# power_board2_v1_0.net
KiCad netlist of a schematic drawn in EAGLE
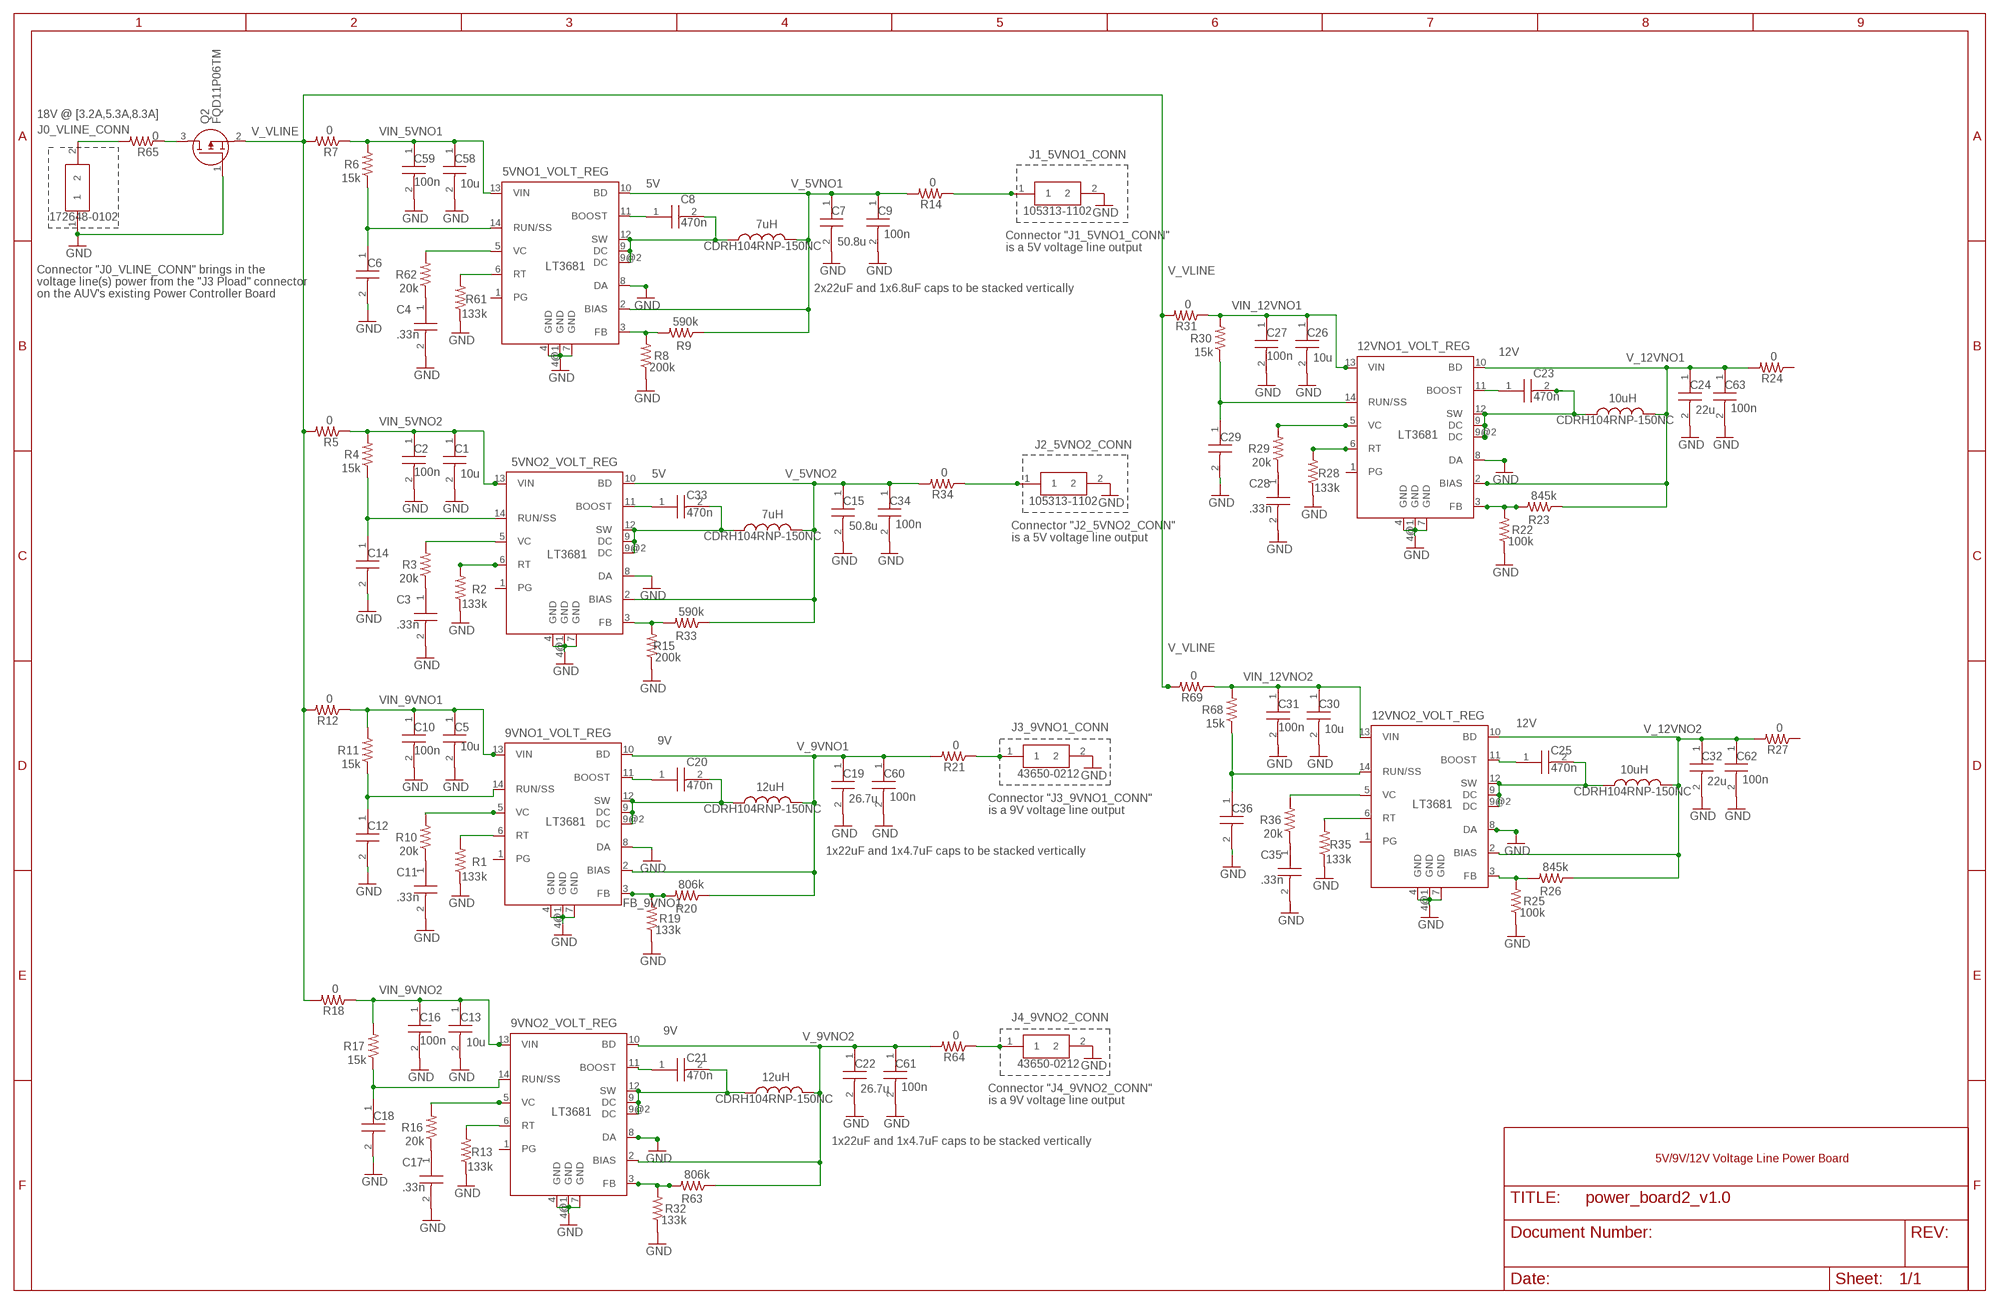
[diagram p0: schematic, sheet 1]

(export (version "E")
  (design (tool "Eeschema 10.0.6"))
  (components
    (comp (ref "5VNO1_VOLT_REG")
      (value "LT3681")
      (footprint "eagle-import:DFN14-4X3DE")
      (fields (field (name "MPN") "LT3681EDE#PBF"))
      (libsource (lib "eagle-import") (part "LT3681"))
    )
    (comp (ref "5VNO2_VOLT_REG")
      (value "LT3681")
      (footprint "eagle-import:DFN14-4X3DE")
      (fields (field (name "MPN") "LT3681EDE#PBF"))
      (libsource (lib "eagle-import") (part "LT3681"))
    )
    (comp (ref "9VNO1_VOLT_REG")
      (value "LT3681")
      (footprint "eagle-import:DFN14-4X3DE")
      (fields (field (name "MPN") "LT3681EDE#PBF"))
      (libsource (lib "eagle-import") (part "LT3681"))
    )
    (comp (ref "9VNO2_VOLT_REG")
      (value "LT3681")
      (footprint "eagle-import:DFN14-4X3DE")
      (fields (field (name "MPN") "LT3681EDE#PBF"))
      (libsource (lib "eagle-import") (part "LT3681"))
    )
    (comp (ref "12VNO1_VOLT_REG")
      (value "LT3681")
      (footprint "eagle-import:DFN14-4X3DE")
      (fields (field (name "MPN") "LT3681EDE#PBF"))
      (libsource (lib "eagle-import") (part "LT3681"))
    )
    (comp (ref "12VNO2_VOLT_REG")
      (value "LT3681")
      (footprint "eagle-import:DFN14-4X3DE")
      (fields (field (name "MPN") "LT3681EDE#PBF"))
      (libsource (lib "eagle-import") (part "LT3681"))
    )
    (comp (ref "C1")
      (value "10u")
      (footprint "eagle-import:CAPC5750X279N")
      (fields
        (field (name "MANUFACTURER_PART_NUMBER") "22201C106KAT2A")
        (field (name "MOUSER_PART_NUMBER") "581-22201C106KAT2A")
      )
      (libsource (lib "eagle-import") (part "22201C106KAT2A"))
    )
    (comp (ref "C2")
      (value "100n")
      (footprint "eagle-import:CAPC1608X90N")
      (fields
        (field (name "MANUFACTURER_PART_NUMBER") "06031C104KAT2A")
        (field (name "MOUSER_PART_NUMBER") "581-06031C104KAT2A")
      )
      (libsource (lib "eagle-import") (part "06031C104KAT2A"))
    )
    (comp (ref "C3")
      (value ".33n")
      (footprint "eagle-import:CAPC2012X140N")
      (fields
        (field (name "MANUFACTURER_PART_NUMBER") "08053C334KAT2A")
        (field (name "MOUSER_PART_NUMBER") "581-08053C334KAT2A")
        (field (name "RS_PART_NUMBER") "1747387")
      )
      (libsource (lib "eagle-import") (part "08053C334KAT2A"))
    )
    (comp (ref "C4")
      (value ".33n")
      (footprint "eagle-import:CAPC2012X140N")
      (fields
        (field (name "MANUFACTURER_PART_NUMBER") "08053C334KAT2A")
        (field (name "MOUSER_PART_NUMBER") "581-08053C334KAT2A")
        (field (name "RS_PART_NUMBER") "1747387")
      )
      (libsource (lib "eagle-import") (part "08053C334KAT2A"))
    )
    (comp (ref "C5")
      (value "10u")
      (footprint "eagle-import:CAPC5750X279N")
      (fields
        (field (name "MANUFACTURER_PART_NUMBER") "22201C106KAT2A")
        (field (name "MOUSER_PART_NUMBER") "581-22201C106KAT2A")
      )
      (libsource (lib "eagle-import") (part "22201C106KAT2A"))
    )
    (comp (ref "C6")
      (value "220n")
      (footprint "eagle-import:CAPC2012X140N")
      (fields
        (field (name "MANUFACTURER_PART_NUMBER") "08051C224KAT2A")
        (field (name "MOUSER_PART_NUMBER") "581-08051C224KAT2A")
      )
      (libsource (lib "eagle-import") (part "08051C224KAT2A"))
    )
    (comp (ref "C7")
      (value "50.8u")
      (footprint "eagle-import:CAPC3225X279N")
      (fields
        (field (name "MANUFACTURER_PART_NUMBER") "12103C226KAT2A")
        (field (name "MOUSER_PART_NUMBER") "581-12103C226KAT2A")
      )
      (libsource (lib "eagle-import") (part "12103C226KAT2A"))
    )
    (comp (ref "C8")
      (value "470n")
      (footprint "eagle-import:CAPC1608X90N")
      (fields
        (field (name "MANUFACTURER_PART_NUMBER") "06033C474JAT2A")
        (field (name "MOUSER_PART_NUMBER") "581-06033C474JAT2A")
      )
      (libsource (lib "eagle-import") (part "06033C474JAT2A"))
    )
    (comp (ref "C9")
      (value "100n")
      (footprint "eagle-import:CAPC1608X90N")
      (fields
        (field (name "MANUFACTURER_PART_NUMBER") "06033C104KAT4A")
        (field (name "MOUSER_PART_NUMBER") "581-06033C104KAT4A")
      )
      (libsource (lib "eagle-import") (part "06033C104KAT4A"))
    )
    (comp (ref "C10")
      (value "100n")
      (footprint "eagle-import:CAPC1608X90N")
      (fields
        (field (name "MANUFACTURER_PART_NUMBER") "06031C104KAT2A")
        (field (name "MOUSER_PART_NUMBER") "581-06031C104KAT2A")
      )
      (libsource (lib "eagle-import") (part "06031C104KAT2A"))
    )
    (comp (ref "C11")
      (value ".33n")
      (footprint "eagle-import:CAPC2012X140N")
      (fields
        (field (name "MANUFACTURER_PART_NUMBER") "08053C334KAT2A")
        (field (name "MOUSER_PART_NUMBER") "581-08053C334KAT2A")
        (field (name "RS_PART_NUMBER") "1747387")
      )
      (libsource (lib "eagle-import") (part "08053C334KAT2A"))
    )
    (comp (ref "C12")
      (value "220n")
      (footprint "eagle-import:CAPC2012X140N")
      (fields
        (field (name "MANUFACTURER_PART_NUMBER") "08051C224KAT2A")
        (field (name "MOUSER_PART_NUMBER") "581-08051C224KAT2A")
      )
      (libsource (lib "eagle-import") (part "08051C224KAT2A"))
    )
    (comp (ref "C13")
      (value "10u")
      (footprint "eagle-import:CAPC5750X279N")
      (fields
        (field (name "MANUFACTURER_PART_NUMBER") "22201C106KAT2A")
        (field (name "MOUSER_PART_NUMBER") "581-22201C106KAT2A")
      )
      (libsource (lib "eagle-import") (part "22201C106KAT2A"))
    )
    (comp (ref "C14")
      (value "220n")
      (footprint "eagle-import:CAPC2012X140N")
      (fields
        (field (name "MANUFACTURER_PART_NUMBER") "08051C224KAT2A")
        (field (name "MOUSER_PART_NUMBER") "581-08051C224KAT2A")
      )
      (libsource (lib "eagle-import") (part "08051C224KAT2A"))
    )
    (comp (ref "C15")
      (value "50.8u")
      (footprint "eagle-import:CAPC3225X279N")
      (fields
        (field (name "MANUFACTURER_PART_NUMBER") "12103C226KAT2A")
        (field (name "MOUSER_PART_NUMBER") "581-12103C226KAT2A")
      )
      (libsource (lib "eagle-import") (part "12103C226KAT2A"))
    )
    (comp (ref "C16")
      (value "100n")
      (footprint "eagle-import:CAPC1608X90N")
      (fields
        (field (name "MANUFACTURER_PART_NUMBER") "06031C104KAT2A")
        (field (name "MOUSER_PART_NUMBER") "581-06031C104KAT2A")
      )
      (libsource (lib "eagle-import") (part "06031C104KAT2A"))
    )
    (comp (ref "C17")
      (value ".33n")
      (footprint "eagle-import:CAPC2012X140N")
      (fields
        (field (name "MANUFACTURER_PART_NUMBER") "08053C334KAT2A")
        (field (name "MOUSER_PART_NUMBER") "581-08053C334KAT2A")
        (field (name "RS_PART_NUMBER") "1747387")
      )
      (libsource (lib "eagle-import") (part "08053C334KAT2A"))
    )
    (comp (ref "C18")
      (value "220n")
      (footprint "eagle-import:CAPC2012X140N")
      (fields
        (field (name "MANUFACTURER_PART_NUMBER") "08051C224KAT2A")
        (field (name "MOUSER_PART_NUMBER") "581-08051C224KAT2A")
      )
      (libsource (lib "eagle-import") (part "08051C224KAT2A"))
    )
    (comp (ref "C19")
      (value "26.7u")
      (footprint "eagle-import:CAPC3225X279N")
      (fields
        (field (name "MANUFACTURER_PART_NUMBER") "12103C226KAT2A")
        (field (name "MOUSER_PART_NUMBER") "581-12103C226KAT2A")
      )
      (libsource (lib "eagle-import") (part "12103C226KAT2A"))
    )
    (comp (ref "C20")
      (value "470n")
      (footprint "eagle-import:CAPC1608X90N")
      (fields
        (field (name "MANUFACTURER_PART_NUMBER") "06033C474JAT2A")
        (field (name "MOUSER_PART_NUMBER") "581-06033C474JAT2A")
      )
      (libsource (lib "eagle-import") (part "06033C474JAT2A"))
    )
    (comp (ref "C21")
      (value "470n")
      (footprint "eagle-import:CAPC1608X90N")
      (fields
        (field (name "MANUFACTURER_PART_NUMBER") "06033C474JAT2A")
        (field (name "MOUSER_PART_NUMBER") "581-06033C474JAT2A")
      )
      (libsource (lib "eagle-import") (part "06033C474JAT2A"))
    )
    (comp (ref "C22")
      (value "26.7u")
      (footprint "eagle-import:CAPC3225X279N")
      (fields
        (field (name "MANUFACTURER_PART_NUMBER") "12103C226KAT2A")
        (field (name "MOUSER_PART_NUMBER") "581-12103C226KAT2A")
      )
      (libsource (lib "eagle-import") (part "12103C226KAT2A"))
    )
    (comp (ref "C23")
      (value "470n")
      (footprint "eagle-import:CAPC1608X90N")
      (fields
        (field (name "MANUFACTURER_PART_NUMBER") "06033C474JAT2A")
        (field (name "MOUSER_PART_NUMBER") "581-06033C474JAT2A")
      )
      (libsource (lib "eagle-import") (part "06033C474JAT2A"))
    )
    (comp (ref "C24")
      (value "50.8u")
      (footprint "eagle-import:CAPC3225X279N")
      (fields
        (field (name "MANUFACTURER_PART_NUMBER") "12103C226KAT2A")
        (field (name "MOUSER_PART_NUMBER") "581-12103C226KAT2A")
      )
      (libsource (lib "eagle-import") (part "12103C226KAT2A"))
    )
    (comp (ref "C25")
      (value "470n")
      (footprint "eagle-import:CAPC1608X90N")
      (fields
        (field (name "MANUFACTURER_PART_NUMBER") "06033C474JAT2A")
        (field (name "MOUSER_PART_NUMBER") "581-06033C474JAT2A")
      )
      (libsource (lib "eagle-import") (part "06033C474JAT2A"))
    )
    (comp (ref "C26")
      (value "10u")
      (footprint "eagle-import:CAPC5750X279N")
      (fields
        (field (name "MANUFACTURER_PART_NUMBER") "22201C106KAT2A")
        (field (name "MOUSER_PART_NUMBER") "581-22201C106KAT2A")
      )
      (libsource (lib "eagle-import") (part "22201C106KAT2A"))
    )
    (comp (ref "C27")
      (value "100n")
      (footprint "eagle-import:CAPC1608X90N")
      (fields
        (field (name "MANUFACTURER_PART_NUMBER") "06031C104KAT2A")
        (field (name "MOUSER_PART_NUMBER") "581-06031C104KAT2A")
      )
      (libsource (lib "eagle-import") (part "06031C104KAT2A"))
    )
    (comp (ref "C28")
      (value ".33n")
      (footprint "eagle-import:CAPC2012X140N")
      (fields
        (field (name "MANUFACTURER_PART_NUMBER") "08053C334KAT2A")
        (field (name "MOUSER_PART_NUMBER") "581-08053C334KAT2A")
        (field (name "RS_PART_NUMBER") "1747387")
      )
      (libsource (lib "eagle-import") (part "08053C334KAT2A"))
    )
    (comp (ref "C29")
      (value "220n")
      (footprint "eagle-import:CAPC2012X140N")
      (fields
        (field (name "MANUFACTURER_PART_NUMBER") "08051C224KAT2A")
        (field (name "MOUSER_PART_NUMBER") "581-08051C224KAT2A")
      )
      (libsource (lib "eagle-import") (part "08051C224KAT2A"))
    )
    (comp (ref "C30")
      (value "10u")
      (footprint "eagle-import:CAPC5750X279N")
      (fields
        (field (name "MANUFACTURER_PART_NUMBER") "22201C106KAT2A")
        (field (name "MOUSER_PART_NUMBER") "581-22201C106KAT2A")
      )
      (libsource (lib "eagle-import") (part "22201C106KAT2A"))
    )
    (comp (ref "C31")
      (value "100n")
      (footprint "eagle-import:CAPC1608X90N")
      (fields
        (field (name "MANUFACTURER_PART_NUMBER") "06031C104KAT2A")
        (field (name "MOUSER_PART_NUMBER") "581-06031C104KAT2A")
      )
      (libsource (lib "eagle-import") (part "06031C104KAT2A"))
    )
    (comp (ref "C32")
      (value "50.8u")
      (footprint "eagle-import:CAPC3225X279N")
      (fields
        (field (name "MANUFACTURER_PART_NUMBER") "12103C226KAT2A")
        (field (name "MOUSER_PART_NUMBER") "581-12103C226KAT2A")
      )
      (libsource (lib "eagle-import") (part "12103C226KAT2A"))
    )
    (comp (ref "C33")
      (value "470n")
      (footprint "eagle-import:CAPC1608X90N")
      (fields
        (field (name "MANUFACTURER_PART_NUMBER") "06033C474JAT2A")
        (field (name "MOUSER_PART_NUMBER") "581-06033C474JAT2A")
      )
      (libsource (lib "eagle-import") (part "06033C474JAT2A"))
    )
    (comp (ref "C34")
      (value "100n")
      (footprint "eagle-import:CAPC1608X90N")
      (fields
        (field (name "MANUFACTURER_PART_NUMBER") "06033C104KAT4A")
        (field (name "MOUSER_PART_NUMBER") "581-06033C104KAT4A")
      )
      (libsource (lib "eagle-import") (part "06033C104KAT4A"))
    )
    (comp (ref "C35")
      (value ".33n")
      (footprint "eagle-import:CAPC2012X140N")
      (fields
        (field (name "MANUFACTURER_PART_NUMBER") "08053C334KAT2A")
        (field (name "MOUSER_PART_NUMBER") "581-08053C334KAT2A")
        (field (name "RS_PART_NUMBER") "1747387")
      )
      (libsource (lib "eagle-import") (part "08053C334KAT2A"))
    )
    (comp (ref "C36")
      (value "220n")
      (footprint "eagle-import:CAPC2012X140N")
      (fields
        (field (name "MANUFACTURER_PART_NUMBER") "08051C224KAT2A")
        (field (name "MOUSER_PART_NUMBER") "581-08051C224KAT2A")
      )
      (libsource (lib "eagle-import") (part "08051C224KAT2A"))
    )
    (comp (ref "C58")
      (value "10u")
      (footprint "eagle-import:CAPC5750X279N")
      (fields
        (field (name "MANUFACTURER_PART_NUMBER") "22201C106KAT2A")
        (field (name "MOUSER_PART_NUMBER") "581-22201C106KAT2A")
      )
      (libsource (lib "eagle-import") (part "22201C106KAT2A"))
    )
    (comp (ref "C59")
      (value "100n")
      (footprint "eagle-import:CAPC1608X90N")
      (fields
        (field (name "MANUFACTURER_PART_NUMBER") "06031C104KAT2A")
        (field (name "MOUSER_PART_NUMBER") "581-06031C104KAT2A")
      )
      (libsource (lib "eagle-import") (part "06031C104KAT2A"))
    )
    (comp (ref "C60")
      (value "100n")
      (footprint "eagle-import:CAPC1608X90N")
      (fields
        (field (name "MANUFACTURER_PART_NUMBER") "06033C104KAT4A")
        (field (name "MOUSER_PART_NUMBER") "581-06033C104KAT4A")
      )
      (libsource (lib "eagle-import") (part "06033C104KAT4A"))
    )
    (comp (ref "C61")
      (value "100n")
      (footprint "eagle-import:CAPC1608X90N")
      (fields
        (field (name "MANUFACTURER_PART_NUMBER") "06033C104KAT4A")
        (field (name "MOUSER_PART_NUMBER") "581-06033C104KAT4A")
      )
      (libsource (lib "eagle-import") (part "06033C104KAT4A"))
    )
    (comp (ref "C62")
      (value "100n")
      (footprint "eagle-import:CAPC1608X90N")
      (fields
        (field (name "MANUFACTURER_PART_NUMBER") "06033C104KAT4A")
        (field (name "MOUSER_PART_NUMBER") "581-06033C104KAT4A")
      )
      (libsource (lib "eagle-import") (part "06033C104KAT4A"))
    )
    (comp (ref "C63")
      (value "100n")
      (footprint "eagle-import:CAPC1608X90N")
      (fields
        (field (name "MANUFACTURER_PART_NUMBER") "06033C104KAT4A")
        (field (name "MOUSER_PART_NUMBER") "581-06033C104KAT4A")
      )
      (libsource (lib "eagle-import") (part "06033C104KAT4A"))
    )
    (comp (ref "INDUCTOR_2")
      (value "CDRH104RNP-150NC")
      (footprint "eagle-import:INDPM102100X400N")
      (fields (field (name "MOUSER_PART_NUMBER") "851-CDRH104RNP-150NC"))
      (libsource (lib "eagle-import") (part "CDRH104RNP-150NC"))
    )
    (comp (ref "INDUCTOR_4")
      (value "CDRH104RNP-150NC")
      (footprint "eagle-import:INDPM102100X400N")
      (fields (field (name "MOUSER_PART_NUMBER") "851-CDRH104RNP-150NC"))
      (libsource (lib "eagle-import") (part "CDRH104RNP-150NC"))
    )
    (comp (ref "INDUCTOR_5")
      (value "CDRH104RNP-150NC")
      (footprint "eagle-import:INDPM102100X400N")
      (fields (field (name "MOUSER_PART_NUMBER") "851-CDRH104RNP-150NC"))
      (libsource (lib "eagle-import") (part "CDRH104RNP-150NC"))
    )
    (comp (ref "INDUCTOR_6")
      (value "CDRH104RNP-150NC")
      (footprint "eagle-import:INDPM102100X400N")
      (fields (field (name "MOUSER_PART_NUMBER") "851-CDRH104RNP-150NC"))
      (libsource (lib "eagle-import") (part "CDRH104RNP-150NC"))
    )
    (comp (ref "INDUCTOR_7")
      (value "CDRH104RNP-150NC")
      (footprint "eagle-import:INDPM102100X400N")
      (fields (field (name "MOUSER_PART_NUMBER") "851-CDRH104RNP-150NC"))
      (libsource (lib "eagle-import") (part "CDRH104RNP-150NC"))
    )
    (comp (ref "INDUCTOR_8")
      (value "CDRH104RNP-150NC")
      (footprint "eagle-import:INDPM102100X400N")
      (fields (field (name "MOUSER_PART_NUMBER") "851-CDRH104RNP-150NC"))
      (libsource (lib "eagle-import") (part "CDRH104RNP-150NC"))
    )
    (comp (ref "J0_VLINE_CONN")
      (value "172648-0102")
      (footprint "eagle-import:1726480102")
      (fields (field (name "MOUSER_PART_NUMBER") "538-172648-0102"))
      (libsource (lib "eagle-import") (part "172648-0102"))
    )
    (comp (ref "J1_B3_CONN1")
      (value "105313-1102")
      (footprint "eagle-import:1053131102")
      (fields (field (name "MOUSER_PART_NUMBER") "538-105313-1102") (field (name "RS_PART_NUMBER") "1623686"))
      (libsource (lib "eagle-import") (part "105313-1102"))
    )
    (comp (ref "J1_B3_CONN2")
      (value "105313-1102")
      (footprint "eagle-import:1053131102")
      (fields (field (name "MOUSER_PART_NUMBER") "538-105313-1102") (field (name "RS_PART_NUMBER") "1623686"))
      (libsource (lib "eagle-import") (part "105313-1102"))
    )
    (comp (ref "J3_9VNO1_CONN")
      (value "43650-0212")
      (footprint "eagle-import:43650-0214")
      (fields (field (name "MOUSER_PART_NUMBER") "538-43650-0212") (field (name "RS_PART_NUMBER") "4476811P"))
      (libsource (lib "eagle-import") (part "43650-0212"))
    )
    (comp (ref "J4_9VNO2_CONN")
      (value "43650-0212")
      (footprint "eagle-import:43650-0214")
      (fields (field (name "MOUSER_PART_NUMBER") "538-43650-0212") (field (name "RS_PART_NUMBER") "4476811P"))
      (libsource (lib "eagle-import") (part "43650-0212"))
    )
    (comp (ref "Q2")
      (value "FQD11P06TM")
      (footprint "eagle-import:DPAK3-CASE-369AS")
      (fields (field (name "MOUSER_PART_NUMBER") "512-FQD11P06TM") (field (name "RS_PART_NUMBER") "6710949P"))
      (libsource (lib "eagle-import") (part "FQD11P06TM"))
    )
    (comp (ref "R1")
      (value "133k")
      (footprint "eagle-import:R0603")
      (libsource (lib "eagle-import") (part "R-US_R0603"))
    )
    (comp (ref "R2")
      (value "133k")
      (footprint "eagle-import:R0603")
      (libsource (lib "eagle-import") (part "R-US_R0603"))
    )
    (comp (ref "R3")
      (value "20k")
      (footprint "eagle-import:R0603")
      (libsource (lib "eagle-import") (part "R-US_R0603"))
    )
    (comp (ref "R4")
      (value "15k")
      (footprint "eagle-import:R0603")
      (libsource (lib "eagle-import") (part "R-US_R0603"))
    )
    (comp (ref "R5")
      (value "0")
      (footprint "eagle-import:0207_2V")
      (fields (field (name "MFR") "Yageo") (field (name "MPN") "RC0805FR-0710KL"))
      (libsource (lib "eagle-import") (part "R-US_0207/2V"))
    )
    (comp (ref "R6")
      (value "15k")
      (footprint "eagle-import:R0603")
      (libsource (lib "eagle-import") (part "R-US_R0603"))
    )
    (comp (ref "R7")
      (value "0")
      (footprint "eagle-import:0207_2V")
      (fields (field (name "MFR") "Yageo") (field (name "MPN") "RC0805FR-0710KL"))
      (libsource (lib "eagle-import") (part "R-US_0207/2V"))
    )
    (comp (ref "R8")
      (value "200k")
      (footprint "eagle-import:R0603")
      (libsource (lib "eagle-import") (part "R-US_R0603"))
    )
    (comp (ref "R9")
      (value "590k")
      (footprint "eagle-import:R0603")
      (libsource (lib "eagle-import") (part "R-US_R0603"))
    )
    (comp (ref "R10")
      (value "20k")
      (footprint "eagle-import:R0603")
      (libsource (lib "eagle-import") (part "R-US_R0603"))
    )
    (comp (ref "R11")
      (value "15k")
      (footprint "eagle-import:R0603")
      (libsource (lib "eagle-import") (part "R-US_R0603"))
    )
    (comp (ref "R12")
      (value "0")
      (footprint "eagle-import:0207_2V")
      (fields (field (name "MFR") "Yageo") (field (name "MPN") "RC0805FR-0710KL"))
      (libsource (lib "eagle-import") (part "R-US_0207/2V"))
    )
    (comp (ref "R13")
      (value "133k")
      (footprint "eagle-import:R0603")
      (libsource (lib "eagle-import") (part "R-US_R0603"))
    )
    (comp (ref "R14")
      (value "0")
      (footprint "eagle-import:0207_2V")
      (fields (field (name "MFR") "Yageo") (field (name "MPN") "RC0805FR-0710KL"))
      (libsource (lib "eagle-import") (part "R-US_0207/2V"))
    )
    (comp (ref "R15")
      (value "200k")
      (footprint "eagle-import:R0603")
      (libsource (lib "eagle-import") (part "R-US_R0603"))
    )
    (comp (ref "R16")
      (value "20k")
      (footprint "eagle-import:R0603")
      (libsource (lib "eagle-import") (part "R-US_R0603"))
    )
    (comp (ref "R17")
      (value "15k")
      (footprint "eagle-import:R0603")
      (libsource (lib "eagle-import") (part "R-US_R0603"))
    )
    (comp (ref "R18")
      (value "0")
      (footprint "eagle-import:0207_2V")
      (fields (field (name "MFR") "Yageo") (field (name "MPN") "RC0805FR-0710KL"))
      (libsource (lib "eagle-import") (part "R-US_0207/2V"))
    )
    (comp (ref "R19")
      (value "133k")
      (footprint "eagle-import:R0603")
      (libsource (lib "eagle-import") (part "R-US_R0603"))
    )
    (comp (ref "R20")
      (value "806k")
      (footprint "eagle-import:R0603")
      (libsource (lib "eagle-import") (part "R-US_R0603"))
    )
    (comp (ref "R21")
      (value "0")
      (footprint "eagle-import:0207_2V")
      (fields (field (name "MFR") "Yageo") (field (name "MPN") "RC0805FR-0710KL"))
      (libsource (lib "eagle-import") (part "R-US_0207/2V"))
    )
    (comp (ref "R22")
      (value "100k")
      (footprint "eagle-import:R0603")
      (libsource (lib "eagle-import") (part "R-US_R0603"))
    )
    (comp (ref "R23")
      (value "845k")
      (footprint "eagle-import:R0603")
      (libsource (lib "eagle-import") (part "R-US_R0603"))
    )
    (comp (ref "R24")
      (value "0")
      (footprint "eagle-import:0207_2V")
      (fields (field (name "MFR") "Yageo") (field (name "MPN") "RC0805FR-0710KL"))
      (libsource (lib "eagle-import") (part "R-US_0207/2V"))
    )
    (comp (ref "R25")
      (value "100k")
      (footprint "eagle-import:R0603")
      (libsource (lib "eagle-import") (part "R-US_R0603"))
    )
    (comp (ref "R26")
      (value "845k")
      (footprint "eagle-import:R0603")
      (libsource (lib "eagle-import") (part "R-US_R0603"))
    )
    (comp (ref "R27")
      (value "0")
      (footprint "eagle-import:0207_2V")
      (fields (field (name "MFR") "Yageo") (field (name "MPN") "RC0805FR-0710KL"))
      (libsource (lib "eagle-import") (part "R-US_0207/2V"))
    )
    (comp (ref "R28")
      (value "133k")
      (footprint "eagle-import:R0603")
      (libsource (lib "eagle-import") (part "R-US_R0603"))
    )
    (comp (ref "R29")
      (value "20k")
      (footprint "eagle-import:R0603")
      (libsource (lib "eagle-import") (part "R-US_R0603"))
    )
    (comp (ref "R30")
      (value "15k")
      (footprint "eagle-import:R0603")
      (libsource (lib "eagle-import") (part "R-US_R0603"))
    )
    (comp (ref "R31")
      (value "0")
      (footprint "eagle-import:0207_2V")
      (fields (field (name "MFR") "Yageo") (field (name "MPN") "RC0805FR-0710KL"))
      (libsource (lib "eagle-import") (part "R-US_0207/2V"))
    )
    (comp (ref "R32")
      (value "133k")
      (footprint "eagle-import:R0603")
      (libsource (lib "eagle-import") (part "R-US_R0603"))
    )
    (comp (ref "R33")
      (value "590k")
      (footprint "eagle-import:R0603")
      (libsource (lib "eagle-import") (part "R-US_R0603"))
    )
    (comp (ref "R34")
      (value "0")
      (footprint "eagle-import:0207_2V")
      (fields (field (name "MFR") "Yageo") (field (name "MPN") "RC0805FR-0710KL"))
      (libsource (lib "eagle-import") (part "R-US_0207/2V"))
    )
    (comp (ref "R35")
      (value "133k")
      (footprint "eagle-import:R0603")
      (libsource (lib "eagle-import") (part "R-US_R0603"))
    )
    (comp (ref "R36")
      (value "20k")
      (footprint "eagle-import:R0603")
      (libsource (lib "eagle-import") (part "R-US_R0603"))
    )
    (comp (ref "R61")
      (value "133k")
      (footprint "eagle-import:R0603")
      (libsource (lib "eagle-import") (part "R-US_R0603"))
    )
    (comp (ref "R62")
      (value "20k")
      (footprint "eagle-import:R0603")
      (libsource (lib "eagle-import") (part "R-US_R0603"))
    )
    (comp (ref "R63")
      (value "806k")
      (footprint "eagle-import:R0603")
      (libsource (lib "eagle-import") (part "R-US_R0603"))
    )
    (comp (ref "R64")
      (value "0")
      (footprint "eagle-import:0207_2V")
      (fields (field (name "MFR") "Yageo") (field (name "MPN") "RC0805FR-0710KL"))
      (libsource (lib "eagle-import") (part "R-US_0207/2V"))
    )
    (comp (ref "R65")
      (value "0")
      (footprint "eagle-import:0207_2V")
      (fields (field (name "MFR") "Yageo") (field (name "MPN") "RC0805FR-0710KL"))
      (libsource (lib "eagle-import") (part "R-US_0207/2V"))
    )
    (comp (ref "R68")
      (value "15k")
      (footprint "eagle-import:R0603")
      (libsource (lib "eagle-import") (part "R-US_R0603"))
    )
    (comp (ref "R69")
      (value "0")
      (footprint "eagle-import:0207_2V")
      (fields (field (name "MFR") "Yageo") (field (name "MPN") "RC0805FR-0710KL"))
      (libsource (lib "eagle-import") (part "R-US_0207/2V"))
    )
  )
  (nets
    (net (code "1") (name "/FB_9VNO1") (class "Default")
      (node (ref "9VNO1_VOLT_REG") (pin "3") (pinfunction "FB_3") (pintype "input"))
      (node (ref "R19") (pin "2") (pinfunction "2_2") (pintype "passive"))
      (node (ref "R20") (pin "2") (pinfunction "2_2") (pintype "passive"))
    )
    (net (code "2") (name "/VIN_5VNO1") (class "Default")
      (node (ref "5VNO1_VOLT_REG") (pin "13") (pinfunction "VIN_13") (pintype "input"))
      (node (ref "C58") (pin "1") (pinfunction "1_1") (pintype "bidirectional"))
      (node (ref "C59") (pin "1") (pinfunction "1_1") (pintype "bidirectional"))
      (node (ref "R6") (pin "2") (pinfunction "2_2") (pintype "passive"))
      (node (ref "R7") (pin "1") (pinfunction "1_1") (pintype "passive"))
    )
    (net (code "3") (name "/VIN_5VNO2") (class "Default")
      (node (ref "5VNO2_VOLT_REG") (pin "13") (pinfunction "VIN_13") (pintype "input"))
      (node (ref "C1") (pin "1") (pinfunction "1_1") (pintype "bidirectional"))
      (node (ref "C2") (pin "1") (pinfunction "1_1") (pintype "bidirectional"))
      (node (ref "R4") (pin "2") (pinfunction "2_2") (pintype "passive"))
      (node (ref "R5") (pin "1") (pinfunction "1_1") (pintype "passive"))
    )
    (net (code "4") (name "/VIN_9VNO1") (class "Default")
      (node (ref "9VNO1_VOLT_REG") (pin "13") (pinfunction "VIN_13") (pintype "input"))
      (node (ref "C10") (pin "1") (pinfunction "1_1") (pintype "bidirectional"))
      (node (ref "C5") (pin "1") (pinfunction "1_1") (pintype "bidirectional"))
      (node (ref "R11") (pin "2") (pinfunction "2_2") (pintype "passive"))
      (node (ref "R12") (pin "1") (pinfunction "1_1") (pintype "passive"))
    )
    (net (code "5") (name "/VIN_9VNO2") (class "Default")
      (node (ref "9VNO2_VOLT_REG") (pin "13") (pinfunction "VIN_13") (pintype "input"))
      (node (ref "C13") (pin "1") (pinfunction "1_1") (pintype "bidirectional"))
      (node (ref "C16") (pin "1") (pinfunction "1_1") (pintype "bidirectional"))
      (node (ref "R17") (pin "2") (pinfunction "2_2") (pintype "passive"))
      (node (ref "R18") (pin "1") (pinfunction "1_1") (pintype "passive"))
    )
    (net (code "6") (name "/VIN_12VNO1") (class "Default")
      (node (ref "12VNO1_VOLT_REG") (pin "13") (pinfunction "VIN_13") (pintype "input"))
      (node (ref "C26") (pin "1") (pinfunction "1_1") (pintype "bidirectional"))
      (node (ref "C27") (pin "1") (pinfunction "1_1") (pintype "bidirectional"))
      (node (ref "R30") (pin "2") (pinfunction "2_2") (pintype "passive"))
      (node (ref "R31") (pin "1") (pinfunction "1_1") (pintype "passive"))
    )
    (net (code "7") (name "/VIN_12VNO2") (class "Default")
      (node (ref "12VNO2_VOLT_REG") (pin "13") (pinfunction "VIN_13") (pintype "input"))
      (node (ref "C30") (pin "1") (pinfunction "1_1") (pintype "bidirectional"))
      (node (ref "C31") (pin "1") (pinfunction "1_1") (pintype "bidirectional"))
      (node (ref "R68") (pin "2") (pinfunction "2_2") (pintype "passive"))
      (node (ref "R69") (pin "1") (pinfunction "1_1") (pintype "passive"))
    )
    (net (code "8") (name "/V_5VNO1") (class "Default")
      (node (ref "5VNO1_VOLT_REG") (pin "10") (pinfunction "BD_10") (pintype "input"))
      (node (ref "5VNO1_VOLT_REG") (pin "2") (pinfunction "BIAS_2") (pintype "input"))
      (node (ref "C7") (pin "1") (pinfunction "1_1") (pintype "bidirectional"))
      (node (ref "C9") (pin "1") (pinfunction "1_1") (pintype "bidirectional"))
      (node (ref "INDUCTOR_2") (pin "2") (pinfunction "2_2") (pintype "passive"))
      (node (ref "R14") (pin "2") (pinfunction "2_2") (pintype "passive"))
      (node (ref "R9") (pin "1") (pinfunction "1_1") (pintype "passive"))
    )
    (net (code "9") (name "/V_5VNO2") (class "Default")
      (node (ref "5VNO2_VOLT_REG") (pin "10") (pinfunction "BD_10") (pintype "input"))
      (node (ref "5VNO2_VOLT_REG") (pin "2") (pinfunction "BIAS_2") (pintype "input"))
      (node (ref "C15") (pin "1") (pinfunction "1_1") (pintype "bidirectional"))
      (node (ref "C34") (pin "1") (pinfunction "1_1") (pintype "bidirectional"))
      (node (ref "INDUCTOR_4") (pin "2") (pinfunction "2_2") (pintype "passive"))
      (node (ref "R33") (pin "1") (pinfunction "1_1") (pintype "passive"))
      (node (ref "R34") (pin "2") (pinfunction "2_2") (pintype "passive"))
    )
    (net (code "10") (name "/V_9VNO1") (class "Default")
      (node (ref "9VNO1_VOLT_REG") (pin "10") (pinfunction "BD_10") (pintype "input"))
      (node (ref "9VNO1_VOLT_REG") (pin "2") (pinfunction "BIAS_2") (pintype "input"))
      (node (ref "C19") (pin "1") (pinfunction "1_1") (pintype "bidirectional"))
      (node (ref "C60") (pin "1") (pinfunction "1_1") (pintype "bidirectional"))
      (node (ref "INDUCTOR_5") (pin "2") (pinfunction "2_2") (pintype "passive"))
      (node (ref "R20") (pin "1") (pinfunction "1_1") (pintype "passive"))
      (node (ref "R21") (pin "2") (pinfunction "2_2") (pintype "passive"))
    )
    (net (code "11") (name "/V_9VNO2") (class "Default")
      (node (ref "9VNO2_VOLT_REG") (pin "10") (pinfunction "BD_10") (pintype "input"))
      (node (ref "9VNO2_VOLT_REG") (pin "2") (pinfunction "BIAS_2") (pintype "input"))
      (node (ref "C22") (pin "1") (pinfunction "1_1") (pintype "bidirectional"))
      (node (ref "C61") (pin "1") (pinfunction "1_1") (pintype "bidirectional"))
      (node (ref "INDUCTOR_6") (pin "2") (pinfunction "2_2") (pintype "passive"))
      (node (ref "R63") (pin "1") (pinfunction "1_1") (pintype "passive"))
      (node (ref "R64") (pin "2") (pinfunction "2_2") (pintype "passive"))
    )
    (net (code "12") (name "/V_12VNO1") (class "Default")
      (node (ref "12VNO1_VOLT_REG") (pin "10") (pinfunction "BD_10") (pintype "input"))
      (node (ref "12VNO1_VOLT_REG") (pin "2") (pinfunction "BIAS_2") (pintype "input"))
      (node (ref "C24") (pin "1") (pinfunction "1_1") (pintype "bidirectional"))
      (node (ref "C63") (pin "1") (pinfunction "1_1") (pintype "bidirectional"))
      (node (ref "INDUCTOR_7") (pin "2") (pinfunction "2_2") (pintype "passive"))
      (node (ref "R23") (pin "1") (pinfunction "1_1") (pintype "passive"))
      (node (ref "R24") (pin "2") (pinfunction "2_2") (pintype "passive"))
    )
    (net (code "13") (name "/V_12VNO2") (class "Default")
      (node (ref "12VNO2_VOLT_REG") (pin "10") (pinfunction "BD_10") (pintype "input"))
      (node (ref "12VNO2_VOLT_REG") (pin "2") (pinfunction "BIAS_2") (pintype "input"))
      (node (ref "C32") (pin "1") (pinfunction "1_1") (pintype "bidirectional"))
      (node (ref "C62") (pin "1") (pinfunction "1_1") (pintype "bidirectional"))
      (node (ref "INDUCTOR_8") (pin "2") (pinfunction "2_2") (pintype "passive"))
      (node (ref "R26") (pin "1") (pinfunction "1_1") (pintype "passive"))
      (node (ref "R27") (pin "2") (pinfunction "2_2") (pintype "passive"))
    )
    (net (code "14") (name "/V_VLINE") (class "Default")
      (node (ref "Q2") (pin "2") (pinfunction "S_2") (pintype "bidirectional"))
      (node (ref "R12") (pin "2") (pinfunction "2_2") (pintype "passive"))
      (node (ref "R18") (pin "2") (pinfunction "2_2") (pintype "passive"))
      (node (ref "R31") (pin "2") (pinfunction "2_2") (pintype "passive"))
      (node (ref "R5") (pin "2") (pinfunction "2_2") (pintype "passive"))
      (node (ref "R69") (pin "2") (pinfunction "2_2") (pintype "passive"))
      (node (ref "R7") (pin "2") (pinfunction "2_2") (pintype "passive"))
    )
    (net (code "15") (name "GND") (class "Default")
      (node (ref "12VNO1_VOLT_REG") (pin "4") (pinfunction "GND_4") (pintype "input"))
      (node (ref "12VNO1_VOLT_REG") (pin "4@1") (pinfunction "GND_4@1") (pintype "input"))
      (node (ref "12VNO1_VOLT_REG") (pin "7") (pinfunction "GND_7") (pintype "input"))
      (node (ref "12VNO1_VOLT_REG") (pin "8") (pinfunction "DA_8") (pintype "passive"))
      (node (ref "12VNO2_VOLT_REG") (pin "4") (pinfunction "GND_4") (pintype "input"))
      (node (ref "12VNO2_VOLT_REG") (pin "4@1") (pinfunction "GND_4@1") (pintype "input"))
      (node (ref "12VNO2_VOLT_REG") (pin "7") (pinfunction "GND_7") (pintype "input"))
      (node (ref "5VNO1_VOLT_REG") (pin "4") (pinfunction "GND_4") (pintype "input"))
      (node (ref "5VNO1_VOLT_REG") (pin "4@1") (pinfunction "GND_4@1") (pintype "input"))
      (node (ref "5VNO1_VOLT_REG") (pin "7") (pinfunction "GND_7") (pintype "input"))
      (node (ref "5VNO1_VOLT_REG") (pin "8") (pinfunction "DA_8") (pintype "passive"))
      (node (ref "5VNO2_VOLT_REG") (pin "4") (pinfunction "GND_4") (pintype "input"))
      (node (ref "5VNO2_VOLT_REG") (pin "4@1") (pinfunction "GND_4@1") (pintype "input"))
      (node (ref "5VNO2_VOLT_REG") (pin "7") (pinfunction "GND_7") (pintype "input"))
      (node (ref "5VNO2_VOLT_REG") (pin "8") (pinfunction "DA_8") (pintype "passive"))
      (node (ref "9VNO1_VOLT_REG") (pin "4") (pinfunction "GND_4") (pintype "input"))
      (node (ref "9VNO1_VOLT_REG") (pin "4@1") (pinfunction "GND_4@1") (pintype "input"))
      (node (ref "9VNO1_VOLT_REG") (pin "7") (pinfunction "GND_7") (pintype "input"))
      (node (ref "9VNO1_VOLT_REG") (pin "8") (pinfunction "DA_8") (pintype "passive"))
      (node (ref "9VNO2_VOLT_REG") (pin "4") (pinfunction "GND_4") (pintype "input"))
      (node (ref "9VNO2_VOLT_REG") (pin "4@1") (pinfunction "GND_4@1") (pintype "input"))
      (node (ref "9VNO2_VOLT_REG") (pin "7") (pinfunction "GND_7") (pintype "input"))
      (node (ref "9VNO2_VOLT_REG") (pin "8") (pinfunction "DA_8") (pintype "passive"))
      (node (ref "C1") (pin "2") (pinfunction "2_2") (pintype "bidirectional"))
      (node (ref "C10") (pin "2") (pinfunction "2_2") (pintype "bidirectional"))
      (node (ref "C11") (pin "2") (pinfunction "2_2") (pintype "bidirectional"))
      (node (ref "C12") (pin "2") (pinfunction "2_2") (pintype "bidirectional"))
      (node (ref "C13") (pin "2") (pinfunction "2_2") (pintype "bidirectional"))
      (node (ref "C14") (pin "2") (pinfunction "2_2") (pintype "bidirectional"))
      (node (ref "C15") (pin "2") (pinfunction "2_2") (pintype "bidirectional"))
      (node (ref "C16") (pin "2") (pinfunction "2_2") (pintype "bidirectional"))
      (node (ref "C17") (pin "2") (pinfunction "2_2") (pintype "bidirectional"))
      (node (ref "C18") (pin "2") (pinfunction "2_2") (pintype "bidirectional"))
      (node (ref "C19") (pin "2") (pinfunction "2_2") (pintype "bidirectional"))
      (node (ref "C2") (pin "2") (pinfunction "2_2") (pintype "bidirectional"))
      (node (ref "C22") (pin "2") (pinfunction "2_2") (pintype "bidirectional"))
      (node (ref "C24") (pin "2") (pinfunction "2_2") (pintype "bidirectional"))
      (node (ref "C26") (pin "2") (pinfunction "2_2") (pintype "bidirectional"))
      (node (ref "C27") (pin "2") (pinfunction "2_2") (pintype "bidirectional"))
      (node (ref "C28") (pin "2") (pinfunction "2_2") (pintype "bidirectional"))
      (node (ref "C29") (pin "2") (pinfunction "2_2") (pintype "bidirectional"))
      (node (ref "C3") (pin "2") (pinfunction "2_2") (pintype "bidirectional"))
      (node (ref "C30") (pin "2") (pinfunction "2_2") (pintype "bidirectional"))
      (node (ref "C31") (pin "2") (pinfunction "2_2") (pintype "bidirectional"))
      (node (ref "C32") (pin "2") (pinfunction "2_2") (pintype "bidirectional"))
      (node (ref "C34") (pin "2") (pinfunction "2_2") (pintype "bidirectional"))
      (node (ref "C35") (pin "2") (pinfunction "2_2") (pintype "bidirectional"))
      (node (ref "C36") (pin "2") (pinfunction "2_2") (pintype "bidirectional"))
      (node (ref "C4") (pin "2") (pinfunction "2_2") (pintype "bidirectional"))
      (node (ref "C5") (pin "2") (pinfunction "2_2") (pintype "bidirectional"))
      (node (ref "C58") (pin "2") (pinfunction "2_2") (pintype "bidirectional"))
      (node (ref "C59") (pin "2") (pinfunction "2_2") (pintype "bidirectional"))
      (node (ref "C6") (pin "2") (pinfunction "2_2") (pintype "bidirectional"))
      (node (ref "C60") (pin "2") (pinfunction "2_2") (pintype "bidirectional"))
      (node (ref "C61") (pin "2") (pinfunction "2_2") (pintype "bidirectional"))
      (node (ref "C62") (pin "2") (pinfunction "2_2") (pintype "bidirectional"))
      (node (ref "C63") (pin "2") (pinfunction "2_2") (pintype "bidirectional"))
      (node (ref "C7") (pin "2") (pinfunction "2_2") (pintype "bidirectional"))
      (node (ref "C9") (pin "2") (pinfunction "2_2") (pintype "bidirectional"))
      (node (ref "J0_VLINE_CONN") (pin "1") (pinfunction "1_1") (pintype "bidirectional"))
      (node (ref "J1_B3_CONN1") (pin "2") (pinfunction "2_2") (pintype "bidirectional"))
      (node (ref "J1_B3_CONN2") (pin "2") (pinfunction "2_2") (pintype "bidirectional"))
      (node (ref "J3_9VNO1_CONN") (pin "2") (pinfunction "2_2") (pintype "bidirectional"))
      (node (ref "J4_9VNO2_CONN") (pin "2") (pinfunction "2_2") (pintype "bidirectional"))
      (node (ref "Q2") (pin "1") (pinfunction "G_1") (pintype "bidirectional"))
      (node (ref "R1") (pin "1") (pinfunction "1_1") (pintype "passive"))
      (node (ref "R13") (pin "1") (pinfunction "1_1") (pintype "passive"))
      (node (ref "R15") (pin "1") (pinfunction "1_1") (pintype "passive"))
      (node (ref "R19") (pin "1") (pinfunction "1_1") (pintype "passive"))
      (node (ref "R2") (pin "1") (pinfunction "1_1") (pintype "passive"))
      (node (ref "R22") (pin "1") (pinfunction "1_1") (pintype "passive"))
      (node (ref "R25") (pin "1") (pinfunction "1_1") (pintype "passive"))
      (node (ref "R28") (pin "1") (pinfunction "1_1") (pintype "passive"))
      (node (ref "R32") (pin "1") (pinfunction "1_1") (pintype "passive"))
      (node (ref "R35") (pin "1") (pinfunction "1_1") (pintype "passive"))
      (node (ref "R61") (pin "1") (pinfunction "1_1") (pintype "passive"))
      (node (ref "R8") (pin "1") (pinfunction "1_1") (pintype "passive"))
    )
    (net (code "16") (name "Net-(5VNO1_VOLT_REG-BOOST)") (class "Default")
      (node (ref "5VNO1_VOLT_REG") (pin "11") (pinfunction "BOOST_11") (pintype "output"))
      (node (ref "C8") (pin "1") (pinfunction "1_1") (pintype "bidirectional"))
    )
    (net (code "17") (name "Net-(5VNO1_VOLT_REG-FB)") (class "Default")
      (node (ref "5VNO1_VOLT_REG") (pin "3") (pinfunction "FB_3") (pintype "input"))
      (node (ref "R8") (pin "2") (pinfunction "2_2") (pintype "passive"))
      (node (ref "R9") (pin "2") (pinfunction "2_2") (pintype "passive"))
    )
    (net (code "18") (name "Net-(5VNO1_VOLT_REG-RT)") (class "Default")
      (node (ref "5VNO1_VOLT_REG") (pin "6") (pinfunction "RT_6") (pintype "input"))
      (node (ref "R61") (pin "2") (pinfunction "2_2") (pintype "passive"))
    )
    (net (code "19") (name "Net-(5VNO1_VOLT_REG-RUN{slash}SS)") (class "Default")
      (node (ref "5VNO1_VOLT_REG") (pin "14") (pinfunction "RUN/SS_14") (pintype "input"))
      (node (ref "C6") (pin "1") (pinfunction "1_1") (pintype "bidirectional"))
      (node (ref "R6") (pin "1") (pinfunction "1_1") (pintype "passive"))
    )
    (net (code "20") (name "Net-(5VNO1_VOLT_REG-SW)") (class "Default")
      (node (ref "5VNO1_VOLT_REG") (pin "12") (pinfunction "SW_12") (pintype "output"))
      (node (ref "5VNO1_VOLT_REG") (pin "9") (pinfunction "DC_9") (pintype "passive"))
      (node (ref "5VNO1_VOLT_REG") (pin "9@2") (pinfunction "DC_9@2") (pintype "passive"))
      (node (ref "C8") (pin "2") (pinfunction "2_2") (pintype "bidirectional"))
      (node (ref "INDUCTOR_2") (pin "1") (pinfunction "1_1") (pintype "passive"))
    )
    (net (code "21") (name "Net-(5VNO1_VOLT_REG-VC)") (class "Default")
      (node (ref "5VNO1_VOLT_REG") (pin "5") (pinfunction "VC_5") (pintype "output"))
      (node (ref "R62") (pin "2") (pinfunction "2_2") (pintype "passive"))
    )
    (net (code "22") (name "Net-(5VNO2_VOLT_REG-BOOST)") (class "Default")
      (node (ref "5VNO2_VOLT_REG") (pin "11") (pinfunction "BOOST_11") (pintype "output"))
      (node (ref "C33") (pin "1") (pinfunction "1_1") (pintype "bidirectional"))
    )
    (net (code "23") (name "Net-(5VNO2_VOLT_REG-FB)") (class "Default")
      (node (ref "5VNO2_VOLT_REG") (pin "3") (pinfunction "FB_3") (pintype "input"))
      (node (ref "R15") (pin "2") (pinfunction "2_2") (pintype "passive"))
      (node (ref "R33") (pin "2") (pinfunction "2_2") (pintype "passive"))
    )
    (net (code "24") (name "Net-(5VNO2_VOLT_REG-RT)") (class "Default")
      (node (ref "5VNO2_VOLT_REG") (pin "6") (pinfunction "RT_6") (pintype "input"))
      (node (ref "R2") (pin "2") (pinfunction "2_2") (pintype "passive"))
    )
    (net (code "25") (name "Net-(5VNO2_VOLT_REG-RUN{slash}SS)") (class "Default")
      (node (ref "5VNO2_VOLT_REG") (pin "14") (pinfunction "RUN/SS_14") (pintype "input"))
      (node (ref "C14") (pin "1") (pinfunction "1_1") (pintype "bidirectional"))
      (node (ref "R4") (pin "1") (pinfunction "1_1") (pintype "passive"))
    )
    (net (code "26") (name "Net-(5VNO2_VOLT_REG-SW)") (class "Default")
      (node (ref "5VNO2_VOLT_REG") (pin "12") (pinfunction "SW_12") (pintype "output"))
      (node (ref "5VNO2_VOLT_REG") (pin "9") (pinfunction "DC_9") (pintype "passive"))
      (node (ref "5VNO2_VOLT_REG") (pin "9@2") (pinfunction "DC_9@2") (pintype "passive"))
      (node (ref "C33") (pin "2") (pinfunction "2_2") (pintype "bidirectional"))
      (node (ref "INDUCTOR_4") (pin "1") (pinfunction "1_1") (pintype "passive"))
    )
    (net (code "27") (name "Net-(5VNO2_VOLT_REG-VC)") (class "Default")
      (node (ref "5VNO2_VOLT_REG") (pin "5") (pinfunction "VC_5") (pintype "output"))
      (node (ref "R3") (pin "2") (pinfunction "2_2") (pintype "passive"))
    )
    (net (code "28") (name "Net-(9VNO1_VOLT_REG-BOOST)") (class "Default")
      (node (ref "9VNO1_VOLT_REG") (pin "11") (pinfunction "BOOST_11") (pintype "output"))
      (node (ref "C20") (pin "1") (pinfunction "1_1") (pintype "bidirectional"))
    )
    (net (code "29") (name "Net-(9VNO1_VOLT_REG-RT)") (class "Default")
      (node (ref "9VNO1_VOLT_REG") (pin "6") (pinfunction "RT_6") (pintype "input"))
      (node (ref "R1") (pin "2") (pinfunction "2_2") (pintype "passive"))
    )
    (net (code "30") (name "Net-(9VNO1_VOLT_REG-RUN{slash}SS)") (class "Default")
      (node (ref "9VNO1_VOLT_REG") (pin "14") (pinfunction "RUN/SS_14") (pintype "input"))
      (node (ref "C12") (pin "1") (pinfunction "1_1") (pintype "bidirectional"))
      (node (ref "R11") (pin "1") (pinfunction "1_1") (pintype "passive"))
    )
    (net (code "31") (name "Net-(9VNO1_VOLT_REG-SW)") (class "Default")
      (node (ref "9VNO1_VOLT_REG") (pin "12") (pinfunction "SW_12") (pintype "output"))
      (node (ref "9VNO1_VOLT_REG") (pin "9") (pinfunction "DC_9") (pintype "passive"))
      (node (ref "9VNO1_VOLT_REG") (pin "9@2") (pinfunction "DC_9@2") (pintype "passive"))
      (node (ref "C20") (pin "2") (pinfunction "2_2") (pintype "bidirectional"))
      (node (ref "INDUCTOR_5") (pin "1") (pinfunction "1_1") (pintype "passive"))
    )
    (net (code "32") (name "Net-(9VNO1_VOLT_REG-VC)") (class "Default")
      (node (ref "9VNO1_VOLT_REG") (pin "5") (pinfunction "VC_5") (pintype "output"))
      (node (ref "R10") (pin "2") (pinfunction "2_2") (pintype "passive"))
    )
    (net (code "33") (name "Net-(9VNO2_VOLT_REG-BOOST)") (class "Default")
      (node (ref "9VNO2_VOLT_REG") (pin "11") (pinfunction "BOOST_11") (pintype "output"))
      (node (ref "C21") (pin "1") (pinfunction "1_1") (pintype "bidirectional"))
    )
    (net (code "34") (name "Net-(9VNO2_VOLT_REG-FB)") (class "Default")
      (node (ref "9VNO2_VOLT_REG") (pin "3") (pinfunction "FB_3") (pintype "input"))
      (node (ref "R32") (pin "2") (pinfunction "2_2") (pintype "passive"))
      (node (ref "R63") (pin "2") (pinfunction "2_2") (pintype "passive"))
    )
    (net (code "35") (name "Net-(9VNO2_VOLT_REG-RT)") (class "Default")
      (node (ref "9VNO2_VOLT_REG") (pin "6") (pinfunction "RT_6") (pintype "input"))
      (node (ref "R13") (pin "2") (pinfunction "2_2") (pintype "passive"))
    )
    (net (code "36") (name "Net-(9VNO2_VOLT_REG-RUN{slash}SS)") (class "Default")
      (node (ref "9VNO2_VOLT_REG") (pin "14") (pinfunction "RUN/SS_14") (pintype "input"))
      (node (ref "C18") (pin "1") (pinfunction "1_1") (pintype "bidirectional"))
      (node (ref "R17") (pin "1") (pinfunction "1_1") (pintype "passive"))
    )
    (net (code "37") (name "Net-(9VNO2_VOLT_REG-SW)") (class "Default")
      (node (ref "9VNO2_VOLT_REG") (pin "12") (pinfunction "SW_12") (pintype "output"))
      (node (ref "9VNO2_VOLT_REG") (pin "9") (pinfunction "DC_9") (pintype "passive"))
      (node (ref "9VNO2_VOLT_REG") (pin "9@2") (pinfunction "DC_9@2") (pintype "passive"))
      (node (ref "C21") (pin "2") (pinfunction "2_2") (pintype "bidirectional"))
      (node (ref "INDUCTOR_6") (pin "1") (pinfunction "1_1") (pintype "passive"))
    )
    (net (code "38") (name "Net-(9VNO2_VOLT_REG-VC)") (class "Default")
      (node (ref "9VNO2_VOLT_REG") (pin "5") (pinfunction "VC_5") (pintype "output"))
      (node (ref "R16") (pin "2") (pinfunction "2_2") (pintype "passive"))
    )
    (net (code "39") (name "Net-(12VNO1_VOLT_REG-BOOST)") (class "Default")
      (node (ref "12VNO1_VOLT_REG") (pin "11") (pinfunction "BOOST_11") (pintype "output"))
      (node (ref "C23") (pin "1") (pinfunction "1_1") (pintype "bidirectional"))
    )
    (net (code "40") (name "Net-(12VNO1_VOLT_REG-FB)") (class "Default")
      (node (ref "12VNO1_VOLT_REG") (pin "3") (pinfunction "FB_3") (pintype "input"))
      (node (ref "R22") (pin "2") (pinfunction "2_2") (pintype "passive"))
      (node (ref "R23") (pin "2") (pinfunction "2_2") (pintype "passive"))
    )
    (net (code "41") (name "Net-(12VNO1_VOLT_REG-RT)") (class "Default")
      (node (ref "12VNO1_VOLT_REG") (pin "6") (pinfunction "RT_6") (pintype "input"))
      (node (ref "R28") (pin "2") (pinfunction "2_2") (pintype "passive"))
    )
    (net (code "42") (name "Net-(12VNO1_VOLT_REG-RUN{slash}SS)") (class "Default")
      (node (ref "12VNO1_VOLT_REG") (pin "14") (pinfunction "RUN/SS_14") (pintype "input"))
      (node (ref "C29") (pin "1") (pinfunction "1_1") (pintype "bidirectional"))
      (node (ref "R30") (pin "1") (pinfunction "1_1") (pintype "passive"))
    )
    (net (code "43") (name "Net-(12VNO1_VOLT_REG-SW)") (class "Default")
      (node (ref "12VNO1_VOLT_REG") (pin "12") (pinfunction "SW_12") (pintype "output"))
      (node (ref "12VNO1_VOLT_REG") (pin "9") (pinfunction "DC_9") (pintype "passive"))
      (node (ref "12VNO1_VOLT_REG") (pin "9@2") (pinfunction "DC_9@2") (pintype "passive"))
      (node (ref "C23") (pin "2") (pinfunction "2_2") (pintype "bidirectional"))
      (node (ref "INDUCTOR_7") (pin "1") (pinfunction "1_1") (pintype "passive"))
    )
    (net (code "44") (name "Net-(12VNO1_VOLT_REG-VC)") (class "Default")
      (node (ref "12VNO1_VOLT_REG") (pin "5") (pinfunction "VC_5") (pintype "output"))
      (node (ref "R29") (pin "2") (pinfunction "2_2") (pintype "passive"))
    )
    (net (code "45") (name "Net-(12VNO2_VOLT_REG-BOOST)") (class "Default")
      (node (ref "12VNO2_VOLT_REG") (pin "11") (pinfunction "BOOST_11") (pintype "output"))
      (node (ref "C25") (pin "1") (pinfunction "1_1") (pintype "bidirectional"))
    )
    (net (code "46") (name "Net-(12VNO2_VOLT_REG-FB)") (class "Default")
      (node (ref "12VNO2_VOLT_REG") (pin "3") (pinfunction "FB_3") (pintype "input"))
      (node (ref "R25") (pin "2") (pinfunction "2_2") (pintype "passive"))
      (node (ref "R26") (pin "2") (pinfunction "2_2") (pintype "passive"))
    )
    (net (code "47") (name "Net-(12VNO2_VOLT_REG-RT)") (class "Default")
      (node (ref "12VNO2_VOLT_REG") (pin "6") (pinfunction "RT_6") (pintype "input"))
      (node (ref "R35") (pin "2") (pinfunction "2_2") (pintype "passive"))
    )
    (net (code "48") (name "Net-(12VNO2_VOLT_REG-RUN{slash}SS)") (class "Default")
      (node (ref "12VNO2_VOLT_REG") (pin "14") (pinfunction "RUN/SS_14") (pintype "input"))
      (node (ref "C36") (pin "1") (pinfunction "1_1") (pintype "bidirectional"))
      (node (ref "R68") (pin "1") (pinfunction "1_1") (pintype "passive"))
    )
    (net (code "49") (name "Net-(12VNO2_VOLT_REG-SW)") (class "Default")
      (node (ref "12VNO2_VOLT_REG") (pin "12") (pinfunction "SW_12") (pintype "output"))
      (node (ref "12VNO2_VOLT_REG") (pin "9") (pinfunction "DC_9") (pintype "passive"))
      (node (ref "12VNO2_VOLT_REG") (pin "9@2") (pinfunction "DC_9@2") (pintype "passive"))
      (node (ref "C25") (pin "2") (pinfunction "2_2") (pintype "bidirectional"))
      (node (ref "INDUCTOR_8") (pin "1") (pinfunction "1_1") (pintype "passive"))
    )
    (net (code "50") (name "Net-(12VNO2_VOLT_REG-VC)") (class "Default")
      (node (ref "12VNO2_VOLT_REG") (pin "5") (pinfunction "VC_5") (pintype "output"))
      (node (ref "R36") (pin "2") (pinfunction "2_2") (pintype "passive"))
    )
    (net (code "51") (name "Net-(C3-Pad1)") (class "Default")
      (node (ref "C3") (pin "1") (pinfunction "1_1") (pintype "bidirectional"))
      (node (ref "R3") (pin "1") (pinfunction "1_1") (pintype "passive"))
    )
    (net (code "52") (name "Net-(C4-Pad1)") (class "Default")
      (node (ref "C4") (pin "1") (pinfunction "1_1") (pintype "bidirectional"))
      (node (ref "R62") (pin "1") (pinfunction "1_1") (pintype "passive"))
    )
    (net (code "53") (name "Net-(C11-Pad1)") (class "Default")
      (node (ref "C11") (pin "1") (pinfunction "1_1") (pintype "bidirectional"))
      (node (ref "R10") (pin "1") (pinfunction "1_1") (pintype "passive"))
    )
    (net (code "54") (name "Net-(C17-Pad1)") (class "Default")
      (node (ref "C17") (pin "1") (pinfunction "1_1") (pintype "bidirectional"))
      (node (ref "R16") (pin "1") (pinfunction "1_1") (pintype "passive"))
    )
    (net (code "55") (name "Net-(C28-Pad1)") (class "Default")
      (node (ref "C28") (pin "1") (pinfunction "1_1") (pintype "bidirectional"))
      (node (ref "R29") (pin "1") (pinfunction "1_1") (pintype "passive"))
    )
    (net (code "56") (name "Net-(C35-Pad1)") (class "Default")
      (node (ref "C35") (pin "1") (pinfunction "1_1") (pintype "bidirectional"))
      (node (ref "R36") (pin "1") (pinfunction "1_1") (pintype "passive"))
    )
    (net (code "57") (name "Net-(J0_VLINE_CONN-Pad2)") (class "Default")
      (node (ref "J0_VLINE_CONN") (pin "2") (pinfunction "2_2") (pintype "bidirectional"))
      (node (ref "R65") (pin "2") (pinfunction "2_2") (pintype "passive"))
    )
    (net (code "58") (name "Net-(J1_B3_CONN1-Pad1)") (class "Default")
      (node (ref "J1_B3_CONN1") (pin "1") (pinfunction "1_1") (pintype "bidirectional"))
      (node (ref "R14") (pin "1") (pinfunction "1_1") (pintype "passive"))
    )
    (net (code "59") (name "Net-(J1_B3_CONN2-Pad1)") (class "Default")
      (node (ref "J1_B3_CONN2") (pin "1") (pinfunction "1_1") (pintype "bidirectional"))
      (node (ref "R34") (pin "1") (pinfunction "1_1") (pintype "passive"))
    )
    (net (code "60") (name "Net-(J3_9VNO1_CONN-Pad1)") (class "Default")
      (node (ref "J3_9VNO1_CONN") (pin "1") (pinfunction "1_1") (pintype "bidirectional"))
      (node (ref "R21") (pin "1") (pinfunction "1_1") (pintype "passive"))
    )
    (net (code "61") (name "Net-(J4_9VNO2_CONN-Pad1)") (class "Default")
      (node (ref "J4_9VNO2_CONN") (pin "1") (pinfunction "1_1") (pintype "bidirectional"))
      (node (ref "R64") (pin "1") (pinfunction "1_1") (pintype "passive"))
    )
    (net (code "62") (name "Net-(Q2-D)") (class "Default")
      (node (ref "Q2") (pin "3") (pinfunction "D_3") (pintype "bidirectional"))
      (node (ref "R65") (pin "1") (pinfunction "1_1") (pintype "passive"))
    )
    (net (code "63") (name "unconnected-(5VNO1_VOLT_REG-PG-Pad1)") (class "Default")
      (node (ref "5VNO1_VOLT_REG") (pin "1") (pinfunction "PG_1") (pintype "open_collector"))
    )
    (net (code "64") (name "unconnected-(5VNO2_VOLT_REG-PG-Pad1)") (class "Default")
      (node (ref "5VNO2_VOLT_REG") (pin "1") (pinfunction "PG_1") (pintype "open_collector"))
    )
    (net (code "65") (name "unconnected-(9VNO1_VOLT_REG-PG-Pad1)") (class "Default")
      (node (ref "9VNO1_VOLT_REG") (pin "1") (pinfunction "PG_1") (pintype "open_collector"))
    )
    (net (code "66") (name "unconnected-(9VNO2_VOLT_REG-PG-Pad1)") (class "Default")
      (node (ref "9VNO2_VOLT_REG") (pin "1") (pinfunction "PG_1") (pintype "open_collector"))
    )
    (net (code "67") (name "unconnected-(12VNO1_VOLT_REG-PG-Pad1)") (class "Default")
      (node (ref "12VNO1_VOLT_REG") (pin "1") (pinfunction "PG_1") (pintype "open_collector"))
    )
    (net (code "68") (name "unconnected-(12VNO2_VOLT_REG-DA-Pad8)") (class "Default")
      (node (ref "12VNO2_VOLT_REG") (pin "8") (pinfunction "DA_8") (pintype "passive"))
    )
    (net (code "69") (name "unconnected-(12VNO2_VOLT_REG-PG-Pad1)") (class "Default")
      (node (ref "12VNO2_VOLT_REG") (pin "1") (pinfunction "PG_1") (pintype "open_collector"))
    )
    (net (code "70") (name "unconnected-(R24-Pad1)") (class "Default")
      (node (ref "R24") (pin "1") (pinfunction "1_1") (pintype "passive"))
    )
    (net (code "71") (name "unconnected-(R27-Pad1)") (class "Default")
      (node (ref "R27") (pin "1") (pinfunction "1_1") (pintype "passive"))
    )
  )
)
